# driver_21_aldo_1.net
KiCad netlist of a schematic drawn in EAGLE
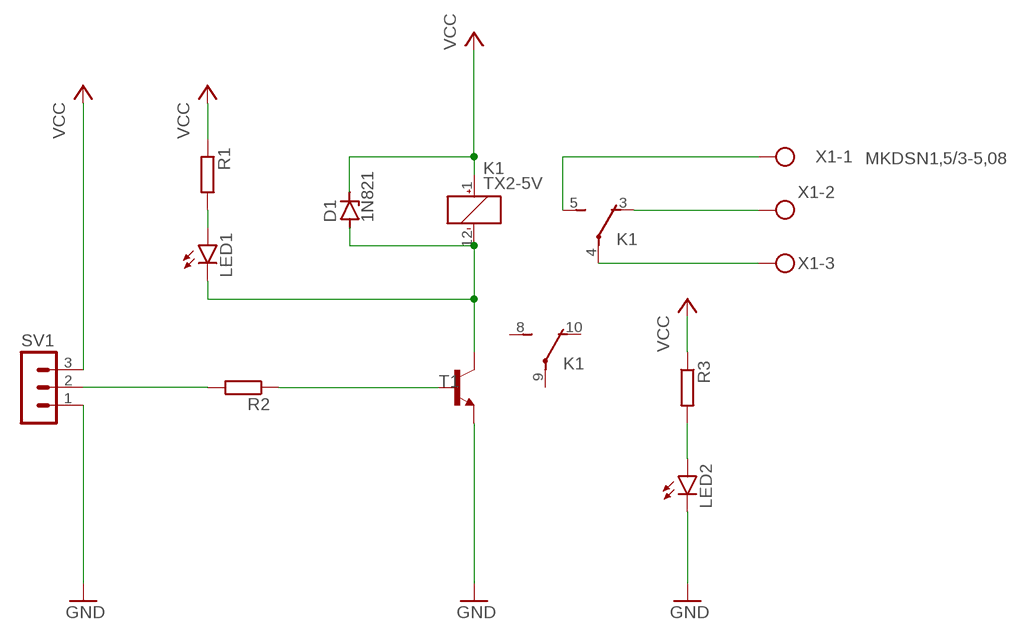
[diagram p0: schematic, sheet 1]

(export (version "E")
  (design (tool "Eeschema 10.0.6"))
  (components
    (comp (ref "D1")
      (value "1N821")
      (footprint "eagle-import:DO35Z10")
      (libsource (lib "eagle-import") (part "1N821"))
    )
    (comp (ref "K1")
      (value "TX2-5V")
      (footprint "eagle-import:TX2")
      (fields (field (name "MF") "AROMAT/ MATSUSHITA"))
      (libsource (lib "eagle-import") (part "TX2?-5V"))
    )
    (comp (ref "LED1")
      (value "LED3MM")
      (footprint "eagle-import:LED3MM")
      (libsource (lib "eagle-import") (part "LED3MM"))
    )
    (comp (ref "LED2")
      (value "LED3MM")
      (footprint "eagle-import:LED3MM")
      (libsource (lib "eagle-import") (part "LED3MM"))
    )
    (comp (ref "R1")
      (value "R-EU_0204/2V")
      (footprint "eagle-import:0204V")
      (libsource (lib "eagle-import") (part "R-EU_0204/2V"))
    )
    (comp (ref "R2")
      (value "R-EU_0204/2V")
      (footprint "eagle-import:0204V")
      (libsource (lib "eagle-import") (part "R-EU_0204/2V"))
    )
    (comp (ref "R3")
      (value "R-EU_0204/2V")
      (footprint "eagle-import:0204V")
      (libsource (lib "eagle-import") (part "R-EU_0204/2V"))
    )
    (comp (ref "SV1")
      (value "MA03-1")
      (footprint "eagle-import:MA03-1")
      (libsource (lib "eagle-import") (part "MA03-1"))
    )
    (comp (ref "T1")
      (value "-NPN-TO92")
      (footprint "eagle-import:TO92")
      (libsource (lib "eagle-import") (part "-NPN-TO92"))
    )
    (comp (ref "X1")
      (value "MKDSN1,5/3-5,08")
      (footprint "eagle-import:MKDSN1,5_3-5,08")
      (libsource (lib "eagle-import") (part "MKDSN1,5/3-5,08"))
    )
  )
  (nets
    (net (code "1") (name "GND") (class "Default")
      (node (ref "LED2") (pin "K") (pinfunction "C_K") (pintype "passive"))
      (node (ref "SV1") (pin "1") (pinfunction "1_1") (pintype "passive"))
      (node (ref "T1") (pin "1") (pinfunction "E_1") (pintype "passive"))
    )
    (net (code "2") (name "Net-(K1A-O)") (class "Default")
      (node (ref "K1") (pin "3") (pinfunction "O_3") (pintype "passive"))
      (node (ref "X1") (pin "2") (pinfunction "KL_2") (pintype "passive"))
    )
    (net (code "3") (name "Net-(K1A-P)") (class "Default")
      (node (ref "K1") (pin "4") (pinfunction "P_4") (pintype "passive"))
      (node (ref "X1") (pin "3") (pinfunction "KL_3") (pintype "passive"))
    )
    (net (code "4") (name "Net-(K1A-S)") (class "Default")
      (node (ref "K1") (pin "5") (pinfunction "S_5") (pintype "passive"))
      (node (ref "X1") (pin "1") (pinfunction "KL_1") (pintype "passive"))
    )
    (net (code "5") (name "Net-(K1C--)") (class "Default")
      (node (ref "D1") (pin "A") (pinfunction "A_A") (pintype "passive"))
      (node (ref "K1") (pin "12") (pinfunction "-_12") (pintype "passive"))
      (node (ref "LED1") (pin "K") (pinfunction "C_K") (pintype "passive"))
      (node (ref "T1") (pin "3") (pinfunction "C_3") (pintype "passive"))
    )
    (net (code "6") (name "Net-(LED1-PadA)") (class "Default")
      (node (ref "LED1") (pin "A") (pinfunction "A_A") (pintype "passive"))
      (node (ref "R1") (pin "2") (pinfunction "2_2") (pintype "passive"))
    )
    (net (code "7") (name "Net-(LED2-PadA)") (class "Default")
      (node (ref "LED2") (pin "A") (pinfunction "A_A") (pintype "passive"))
      (node (ref "R3") (pin "2") (pinfunction "2_2") (pintype "passive"))
    )
    (net (code "8") (name "Net-(R2-Pad2)") (class "Default")
      (node (ref "R2") (pin "2") (pinfunction "2_2") (pintype "passive"))
      (node (ref "SV1") (pin "2") (pinfunction "2_2") (pintype "passive"))
    )
    (net (code "9") (name "Net-(T1-B)") (class "Default")
      (node (ref "R2") (pin "1") (pinfunction "1_1") (pintype "passive"))
      (node (ref "T1") (pin "2") (pinfunction "B_2") (pintype "passive"))
    )
    (net (code "10") (name "VCC") (class "Default")
      (node (ref "D1") (pin "C") (pinfunction "C_C") (pintype "passive"))
      (node (ref "K1") (pin "1") (pinfunction "+_1") (pintype "passive"))
      (node (ref "R1") (pin "1") (pinfunction "1_1") (pintype "passive"))
      (node (ref "R3") (pin "1") (pinfunction "1_1") (pintype "passive"))
      (node (ref "SV1") (pin "3") (pinfunction "3_3") (pintype "passive"))
    )
    (net (code "11") (name "unconnected-(K1B-O-Pad10)") (class "Default")
      (node (ref "K1") (pin "10") (pinfunction "O_10") (pintype "passive"))
    )
    (net (code "12") (name "unconnected-(K1B-P-Pad9)") (class "Default")
      (node (ref "K1") (pin "9") (pinfunction "P_9") (pintype "passive"))
    )
    (net (code "13") (name "unconnected-(K1B-S-Pad8)") (class "Default")
      (node (ref "K1") (pin "8") (pinfunction "S_8") (pintype "passive"))
    )
  )
)
